# PCB-DDEX-BASE.net
KiCad netlist of a schematic drawn in EAGLE
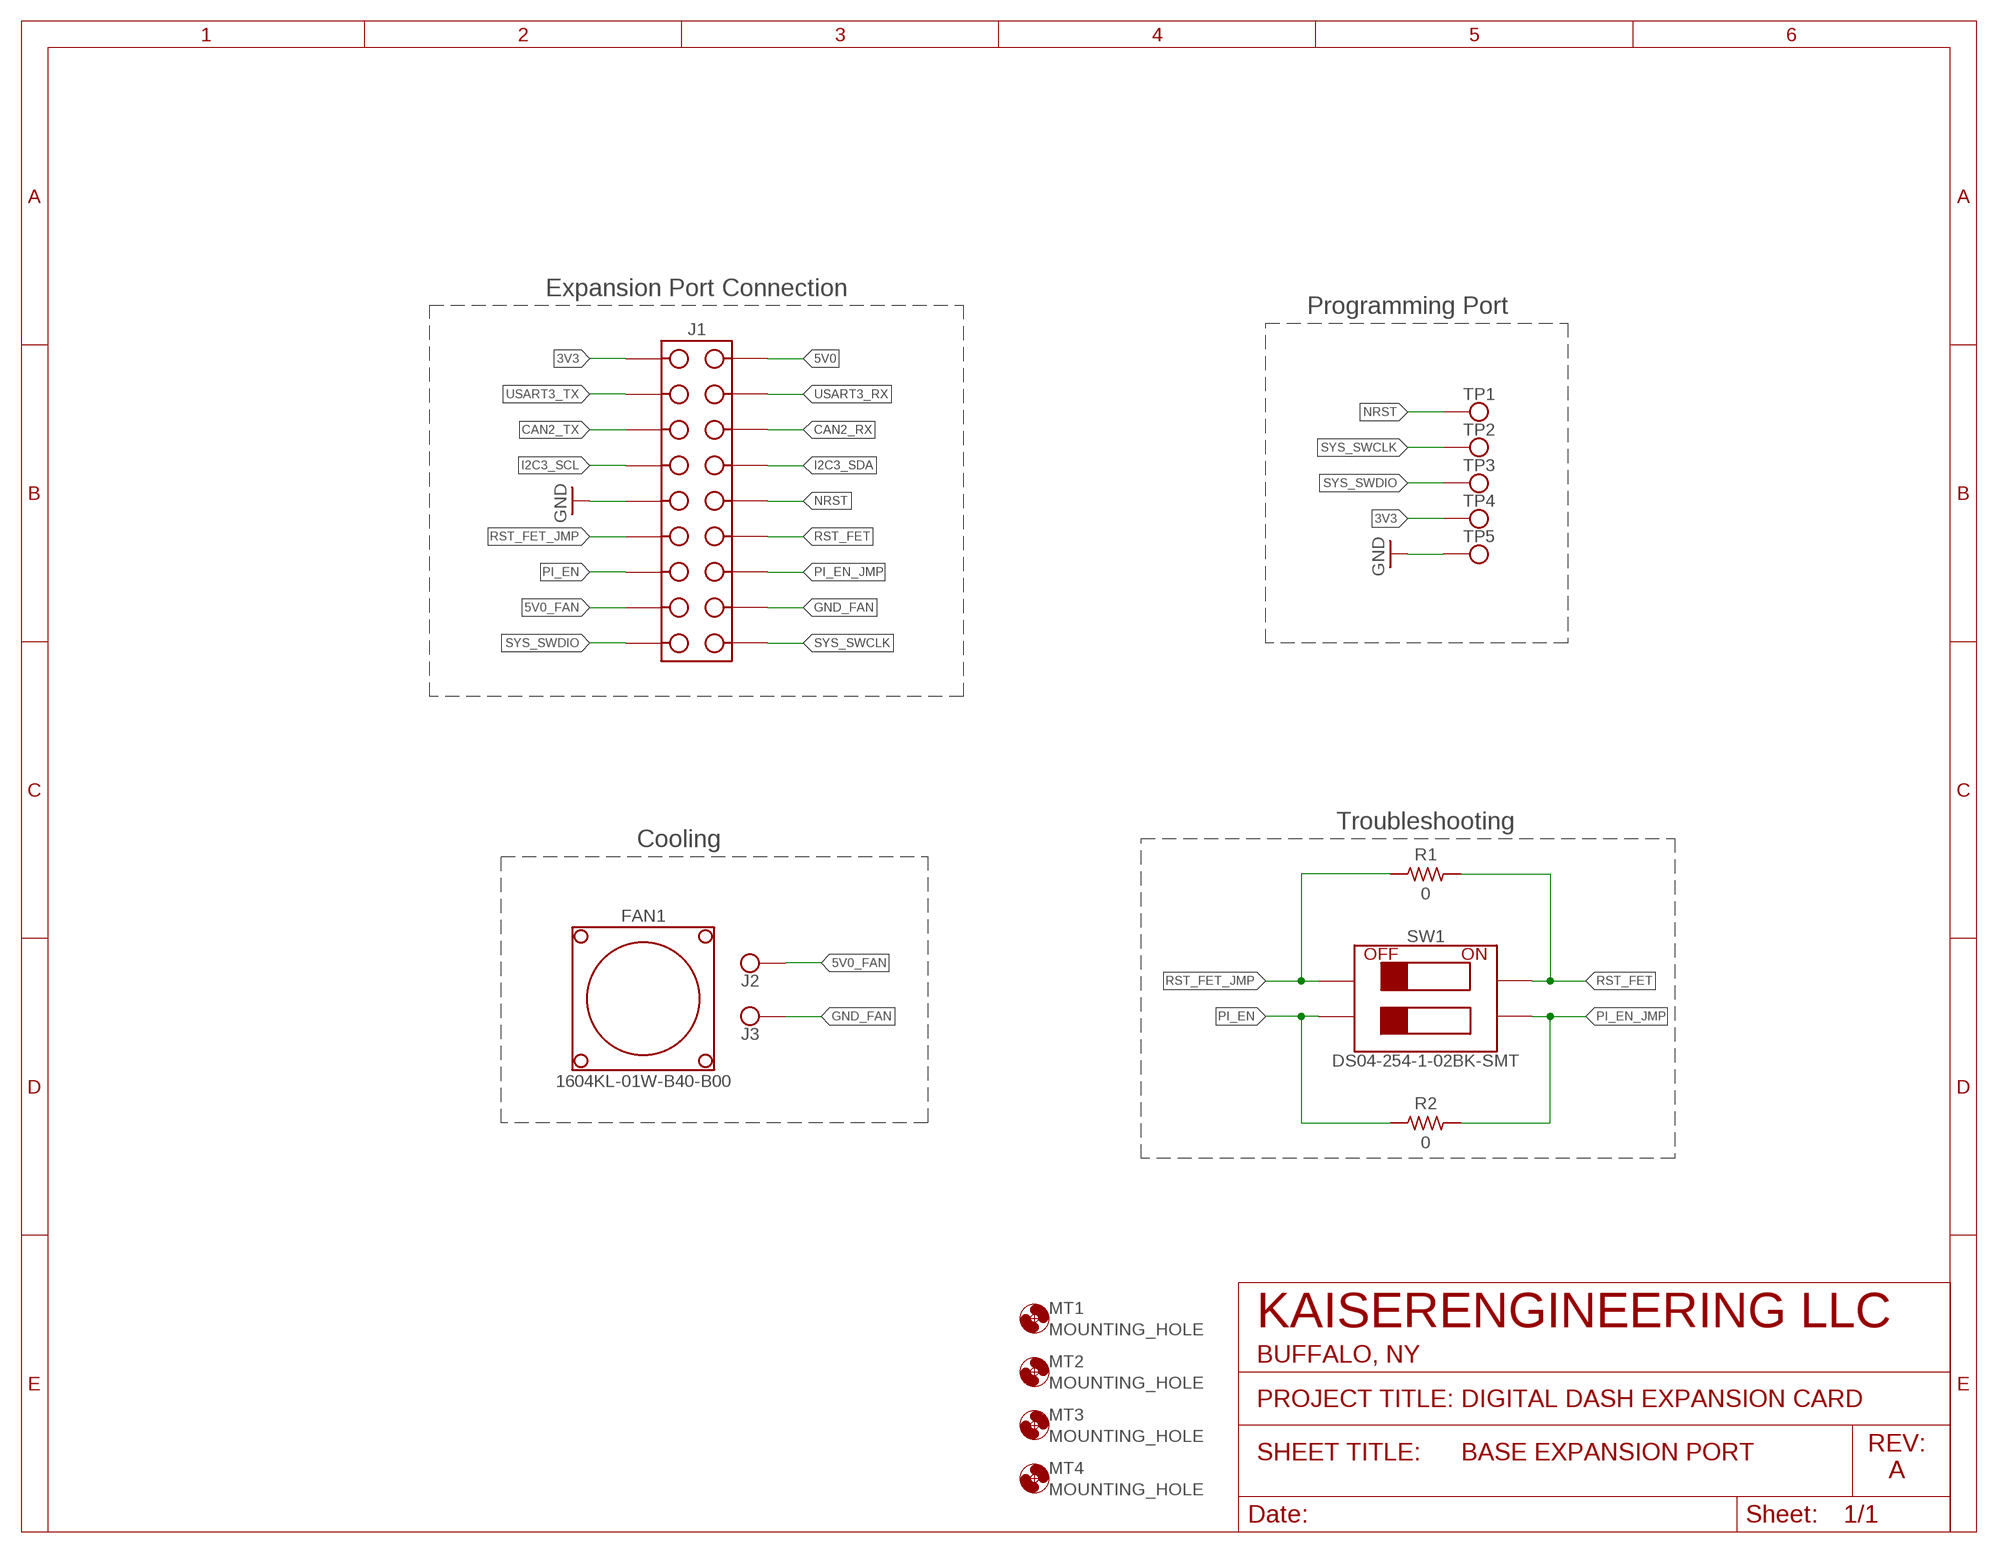
[diagram p0: schematic, sheet 1]

(export (version "E")
  (design (tool "Eeschema 10.0.6"))
  (components
    (comp (ref "FAN1")
      (value "NMB_1604KL-01W-B40-B00")
      (footprint "eagle-import:NMB_40MMX40MMX10MM_FAN")
      (fields (field (name "PN") "1604KL-01W-B40-B00") (field (name "MFG") "NMB"))
      (libsource (lib "eagle-import") (part "NMB_1604KL-01W-B40-B00"))
    )
    (comp (ref "J1")
      (value "HEADER_9X2PIN_VERT")
      (footprint "eagle-import:HEADER_100MIL_9X2")
      (fields (field (name "MFG") "WURTH"))
      (libsource (lib "eagle-import") (part "HEADER_9X2PIN_VERT"))
    )
    (comp (ref "J2")
      (value "SOLDER_POINT")
      (footprint "eagle-import:SMD_PAD_100X200")
      (libsource (lib "eagle-import") (part "SOLDER_POINT"))
    )
    (comp (ref "J3")
      (value "SOLDER_POINT")
      (footprint "eagle-import:SMD_PAD_100X200")
      (libsource (lib "eagle-import") (part "SOLDER_POINT"))
    )
    (comp (ref "MT1")
      (value "MOUNTING_HOLE")
      (footprint "eagle-import:MT_2MM")
      (fields (field (name "MFG") "NA"))
      (libsource (lib "eagle-import") (part "MOUNTING_HOLE"))
    )
    (comp (ref "MT2")
      (value "MOUNTING_HOLE")
      (footprint "eagle-import:MT_2MM")
      (fields (field (name "MFG") "NA"))
      (libsource (lib "eagle-import") (part "MOUNTING_HOLE"))
    )
    (comp (ref "MT3")
      (value "MOUNTING_HOLE")
      (footprint "eagle-import:MT_2MM")
      (fields (field (name "MFG") "NA"))
      (libsource (lib "eagle-import") (part "MOUNTING_HOLE"))
    )
    (comp (ref "MT4")
      (value "MOUNTING_HOLE")
      (footprint "eagle-import:MT_2MM")
      (fields (field (name "MFG") "NA"))
      (libsource (lib "eagle-import") (part "MOUNTING_HOLE"))
    )
    (comp (ref "R1")
      (value "0")
      (footprint "eagle-import:REST-0603")
      (fields (field (name "MFG") "VISHAY"))
      (libsource (lib "eagle-import") (part "0OHM-0603-1%-1/10W"))
    )
    (comp (ref "R2")
      (value "0")
      (footprint "eagle-import:REST-0603")
      (fields (field (name "MFG") "VISHAY"))
      (libsource (lib "eagle-import") (part "0OHM-0603-1%-1/10W"))
    )
    (comp (ref "SW1")
      (value "DIP2_CUI_DS04-254-1-02BK-SMT")
      (footprint "eagle-import:DIP2_SMD_254")
      (fields (field (name "PN") "DS04-254-1-02BK-SMT") (field (name "MFG") "CUI"))
      (libsource (lib "eagle-import") (part "DIP2_CUI_DS04-254-1-02BK-SMT"))
    )
    (comp (ref "TP1")
      (value "SOLDER_POINT_ROUND")
      (footprint "eagle-import:SMD_PAD_ROUND")
      (libsource (lib "eagle-import") (part "SOLDER_POINT_ROUND"))
    )
    (comp (ref "TP2")
      (value "SOLDER_POINT_ROUND")
      (footprint "eagle-import:SMD_PAD_ROUND")
      (libsource (lib "eagle-import") (part "SOLDER_POINT_ROUND"))
    )
    (comp (ref "TP3")
      (value "SOLDER_POINT_ROUND")
      (footprint "eagle-import:SMD_PAD_ROUND")
      (libsource (lib "eagle-import") (part "SOLDER_POINT_ROUND"))
    )
    (comp (ref "TP4")
      (value "SOLDER_POINT_ROUND")
      (footprint "eagle-import:SMD_PAD_ROUND")
      (libsource (lib "eagle-import") (part "SOLDER_POINT_ROUND"))
    )
    (comp (ref "TP5")
      (value "SOLDER_POINT_ROUND")
      (footprint "eagle-import:SMD_PAD_ROUND")
      (libsource (lib "eagle-import") (part "SOLDER_POINT_ROUND"))
    )
  )
  (nets
    (net (code "1") (name "3V3") (class "Default")
      (node (ref "J1") (pin "P$10") (pinfunction "10_P$10") (pintype "bidirectional"))
      (node (ref "TP4") (pin "1") (pinfunction "IN_1") (pintype "bidirectional"))
    )
    (net (code "2") (name "5V0") (class "Default")
      (node (ref "J1") (pin "P$1") (pinfunction "1_P$1") (pintype "bidirectional"))
    )
    (net (code "3") (name "5V0_FAN") (class "Default")
      (node (ref "J1") (pin "P$17") (pinfunction "17_P$17") (pintype "bidirectional"))
      (node (ref "J2") (pin "1") (pinfunction "IN_1") (pintype "bidirectional"))
    )
    (net (code "4") (name "CAN2_RX") (class "Default")
      (node (ref "J1") (pin "P$3") (pinfunction "3_P$3") (pintype "bidirectional"))
    )
    (net (code "5") (name "CAN2_TX") (class "Default")
      (node (ref "J1") (pin "P$12") (pinfunction "12_P$12") (pintype "bidirectional"))
    )
    (net (code "6") (name "GND") (class "Default")
      (node (ref "J1") (pin "P$14") (pinfunction "14_P$14") (pintype "bidirectional"))
      (node (ref "TP5") (pin "1") (pinfunction "IN_1") (pintype "bidirectional"))
    )
    (net (code "7") (name "GND_FAN") (class "Default")
      (node (ref "J1") (pin "P$8") (pinfunction "8_P$8") (pintype "bidirectional"))
      (node (ref "J3") (pin "1") (pinfunction "IN_1") (pintype "bidirectional"))
    )
    (net (code "8") (name "I2C3_SCL") (class "Default")
      (node (ref "J1") (pin "P$13") (pinfunction "13_P$13") (pintype "bidirectional"))
    )
    (net (code "9") (name "I2C3_SDA") (class "Default")
      (node (ref "J1") (pin "P$4") (pinfunction "4_P$4") (pintype "bidirectional"))
    )
    (net (code "10") (name "NRST") (class "Default")
      (node (ref "J1") (pin "P$5") (pinfunction "5_P$5") (pintype "bidirectional"))
      (node (ref "TP1") (pin "1") (pinfunction "IN_1") (pintype "bidirectional"))
    )
    (net (code "11") (name "PI_EN") (class "Default")
      (node (ref "J1") (pin "P$16") (pinfunction "16_P$16") (pintype "bidirectional"))
      (node (ref "R2") (pin "1") (pinfunction "1_1") (pintype "bidirectional"))
      (node (ref "SW1") (pin "3") (pinfunction "P$3_3") (pintype "bidirectional"))
    )
    (net (code "12") (name "PI_EN_JMP") (class "Default")
      (node (ref "J1") (pin "P$7") (pinfunction "7_P$7") (pintype "bidirectional"))
      (node (ref "R2") (pin "2") (pinfunction "2_2") (pintype "bidirectional"))
      (node (ref "SW1") (pin "4") (pinfunction "P$4_4") (pintype "bidirectional"))
    )
    (net (code "13") (name "RST_FET") (class "Default")
      (node (ref "J1") (pin "P$6") (pinfunction "6_P$6") (pintype "bidirectional"))
      (node (ref "R1") (pin "2") (pinfunction "2_2") (pintype "bidirectional"))
      (node (ref "SW1") (pin "2") (pinfunction "P$2_2") (pintype "bidirectional"))
    )
    (net (code "14") (name "RST_FET_JMP") (class "Default")
      (node (ref "J1") (pin "P$15") (pinfunction "15_P$15") (pintype "bidirectional"))
      (node (ref "R1") (pin "1") (pinfunction "1_1") (pintype "bidirectional"))
      (node (ref "SW1") (pin "1") (pinfunction "P$1_1") (pintype "bidirectional"))
    )
    (net (code "15") (name "SYS_SWCLK") (class "Default")
      (node (ref "J1") (pin "P$9") (pinfunction "9_P$9") (pintype "bidirectional"))
      (node (ref "TP2") (pin "1") (pinfunction "IN_1") (pintype "bidirectional"))
    )
    (net (code "16") (name "SYS_SWDIO") (class "Default")
      (node (ref "J1") (pin "P$18") (pinfunction "18_P$18") (pintype "bidirectional"))
      (node (ref "TP3") (pin "1") (pinfunction "IN_1") (pintype "bidirectional"))
    )
    (net (code "17") (name "USART3_RX") (class "Default")
      (node (ref "J1") (pin "P$2") (pinfunction "2_P$2") (pintype "bidirectional"))
    )
    (net (code "18") (name "USART3_TX") (class "Default")
      (node (ref "J1") (pin "P$11") (pinfunction "11_P$11") (pintype "bidirectional"))
    )
  )
)
